# Schematic.net
KiCad netlist of a schematic drawn in Altium Designer
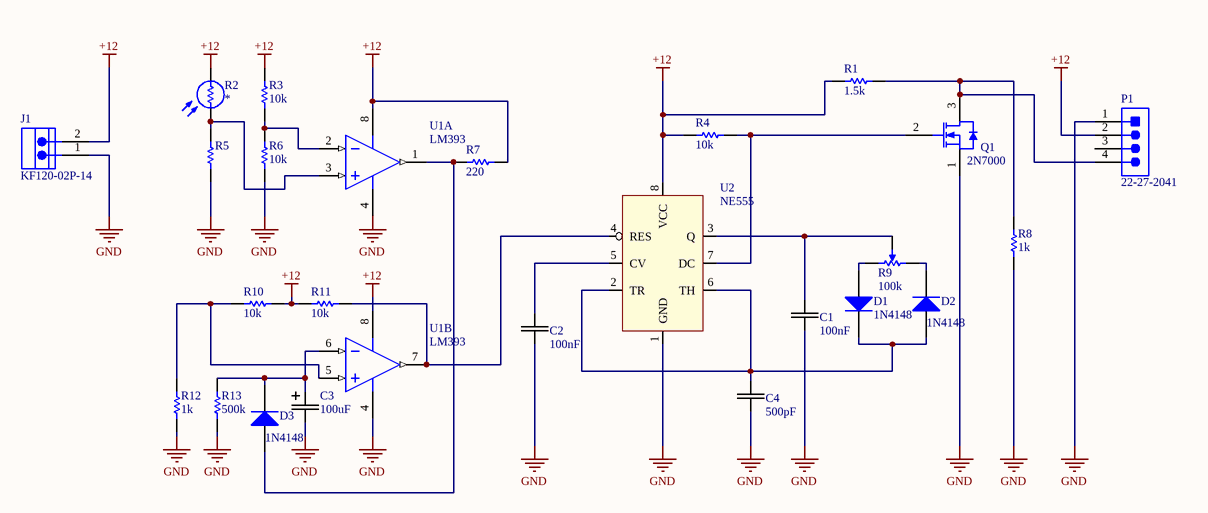
[diagram p0: Schematic.SchDoc]

(export (version "E")
  (design (tool "Eeschema 10.0.6"))
  (components
    (comp (ref "C1")
      (value "CAP_CERAM")
      (footprint "CAP_CERAM")
      (description "Ceramic capacitor")
      (fields (field (name "VAL") "100nF"))
      (libsource (lib "altium-import") (part "root_1_CAP_CERAM_"))
    )
    (comp (ref "C2")
      (value "CAP_CERAM")
      (footprint "CAP_CERAM")
      (description "Ceramic capacitor")
      (fields (field (name "VAL") "100nF"))
      (libsource (lib "altium-import") (part "root_1_CAP_CERAM_"))
    )
    (comp (ref "C3")
      (value "CAP_ELEC_8*11")
      (footprint "CAP_ELEC_8*11")
      (description "Electrolitic capacitor")
      (fields (field (name "VAL") "100uF"))
      (libsource (lib "altium-import") (part "root_1_CAP_ELEC_8*11_"))
    )
    (comp (ref "C4")
      (value "CAP_CERAM")
      (footprint "CAP_CERAM")
      (description "Ceramic capacitor")
      (fields (field (name "VAL") "500pF"))
      (libsource (lib "altium-import") (part "root_1_CAP_CERAM_"))
    )
    (comp (ref "D1")
      (value "1N4148")
      (footprint "DO-41")
      (description "1 A Rectifier Diode, 1000 V, -65 to 175 degC, 2-Pin DO-214AC")
      (fields (field (name "PARTNUMBER") "1N4007") (field (name "MANUFACTURER") "Kesenes"))
      (libsource (lib "altium-import") (part "root_3_1N4007_"))
    )
    (comp (ref "D2")
      (value "1N4148")
      (footprint "DO-41")
      (description "1 A Rectifier Diode, 1000 V, -65 to 175 degC, 2-Pin DO-214AC")
      (fields (field (name "PARTNUMBER") "1N4007") (field (name "MANUFACTURER") "Kesenes"))
      (libsource (lib "altium-import") (part "root_1_1N4007_"))
    )
    (comp (ref "D3")
      (value "1N4148")
      (footprint "DO-41")
      (description "1 A Rectifier Diode, 1000 V, -65 to 175 degC, 2-Pin DO-214AC")
      (fields (field (name "PARTNUMBER") "1N4007") (field (name "MANUFACTURER") "Kesenes"))
      (libsource (lib "altium-import") (part "root_1_1N4007_"))
    )
    (comp (ref "J1")
      (value "KF120-02P-14")
      (footprint "DG301-5.0-02P-1X")
      (fields (field (name "MANUFACTURER") "Cixi KaiFeng") (field (name "CONTACT") "Brass"))
      (libsource (lib "altium-import") (part "root_1_Terminal_2_"))
    )
    (comp (ref "P1")
      (value "22-27-2041")
      (footprint "MOLX-22-27-2041_V")
      (description "Male Header, Pitch 2.54 mm, 1 x 4 Position, Height 11.7 mm, Tail Length 3.56 mm, RoHS, Bulk")
      (fields (field (name "MANUFACTURER") "Molex"))
      (libsource (lib "altium-import") (part "root_0_Molex 1x4 2.54 FAN_"))
    )
    (comp (ref "Q1")
      (value "2N7000")
      (footprint "TO-92A")
      (description "Small Signal MOSFET\r\n200 mAmps, 60 Volts")
      (fields (field (name "MANUFACTURER") "International Rectifier"))
      (libsource (lib "altium-import") (part "root_0_2N7000_"))
    )
    (comp (ref "R1")
      (value "RES-0.125")
      (footprint "RES-0.125")
      (fields (field (name "VAL") "1.5k"))
      (libsource (lib "altium-import") (part "root_2_RES-0.125_"))
    )
    (comp (ref "R2")
      (value "Photoresistor")
      (footprint "Photoresistor")
      (description "PR")
      (fields (field (name "VAL") "*"))
      (libsource (lib "altium-import") (part "root_1_Photoresistor_"))
    )
    (comp (ref "R3")
      (value "RES-0.125")
      (footprint "RES-0.125")
      (fields (field (name "VAL") "10k"))
      (libsource (lib "altium-import") (part "root_1_RES-0.125_"))
    )
    (comp (ref "R4")
      (value "RES-0.125")
      (footprint "RES-0.125")
      (fields (field (name "VAL") "10k"))
      (libsource (lib "altium-import") (part "root_0_RES-0.125_"))
    )
    (comp (ref "R5")
      (value "RES-0.125")
      (footprint "RES-0.125")
      (libsource (lib "altium-import") (part "root_1_RES-0.125_"))
    )
    (comp (ref "R6")
      (value "RES-0.125")
      (footprint "RES-0.125")
      (fields (field (name "VAL") "10k"))
      (libsource (lib "altium-import") (part "root_1_RES-0.125_"))
    )
    (comp (ref "R7")
      (value "RES-0.125")
      (footprint "RES-0.125")
      (fields (field (name "VAL") "220"))
      (libsource (lib "altium-import") (part "root_0_RES-0.125_"))
    )
    (comp (ref "R8")
      (value "RES-0.125")
      (footprint "RES-0.125")
      (fields (field (name "VAL") "1k"))
      (libsource (lib "altium-import") (part "root_1_RES-0.125_"))
    )
    (comp (ref "R9")
      (value "100k")
      (footprint "BOUR-3362P")
      (fields (field (name "Comment") "3296W"))
      (libsource (lib "altium-import") (part "root_2_Potentiometer_"))
    )
    (comp (ref "R10")
      (value "RES-0.125")
      (footprint "RES-0.125")
      (fields (field (name "VAL") "10k"))
      (libsource (lib "altium-import") (part "root_0_RES-0.125_"))
    )
    (comp (ref "R11")
      (value "RES-0.125")
      (footprint "RES-0.125")
      (fields (field (name "VAL") "10k"))
      (libsource (lib "altium-import") (part "root_0_RES-0.125_"))
    )
    (comp (ref "R12")
      (value "RES-0.125")
      (footprint "RES-0.125")
      (fields (field (name "VAL") "1k"))
      (libsource (lib "altium-import") (part "root_1_RES-0.125_"))
    )
    (comp (ref "R13")
      (value "RES-0.125")
      (footprint "RES-0.125")
      (fields (field (name "VAL") "500k"))
      (libsource (lib "altium-import") (part "root_1_RES-0.125_"))
    )
    (comp (ref "U1")
      (value "LM393")
      (footprint "SO-8_N")
      (description "Low Power Low Offset Voltage Dual Comparator, 8-pin Narrow SOIC, Pb-Free")
      (fields (field (name "MANUFACTURER") "Texas Instruments"))
      (libsource (lib "web.skorpio") (part "LM393"))
    )
    (comp (ref "U2")
      (value "NE555")
      (footprint "SOIC8")
      (description "NE555, DIP-8")
      (libsource (lib "altium-import") (part "root_0_NE555_"))
    )
  )
  (nets
    (net (code "1") (name "+12") (class "Default")
      (node (ref "J1") (pin "2") (pinfunction "2_2") (pintype "passive"))
      (node (ref "P1") (pin "2") (pinfunction "2_2") (pintype "passive"))
      (node (ref "R1") (pin "2") (pinfunction "2_2") (pintype "passive"))
      (node (ref "R10") (pin "2") (pinfunction "2_2") (pintype "passive"))
      (node (ref "R11") (pin "1") (pinfunction "1_1") (pintype "passive"))
      (node (ref "R2") (pin "2") (pinfunction "2_2") (pintype "passive"))
      (node (ref "R3") (pin "2") (pinfunction "2_2") (pintype "passive"))
      (node (ref "R4") (pin "1") (pinfunction "1_1") (pintype "passive"))
      (node (ref "R7") (pin "2") (pinfunction "2_2") (pintype "passive"))
      (node (ref "U1") (pin "8") (pinfunction "V+_8") (pintype "power_in"))
      (node (ref "U2") (pin "8") (pinfunction "VCC_8") (pintype "passive"))
    )
    (net (code "2") (name "GND") (class "Default")
      (node (ref "C1") (pin "1") (pinfunction "1_1") (pintype "passive"))
      (node (ref "C2") (pin "1") (pinfunction "1_1") (pintype "passive"))
      (node (ref "C3") (pin "1") (pinfunction "1_1") (pintype "passive"))
      (node (ref "C4") (pin "1") (pinfunction "1_1") (pintype "passive"))
      (node (ref "J1") (pin "1") (pinfunction "1_1") (pintype "passive"))
      (node (ref "P1") (pin "1") (pinfunction "1_1") (pintype "passive"))
      (node (ref "Q1") (pin "1") (pinfunction "S_1") (pintype "passive"))
      (node (ref "R12") (pin "1") (pinfunction "1_1") (pintype "passive"))
      (node (ref "R13") (pin "1") (pinfunction "1_1") (pintype "passive"))
      (node (ref "R5") (pin "1") (pinfunction "1_1") (pintype "passive"))
      (node (ref "R6") (pin "1") (pinfunction "1_1") (pintype "passive"))
      (node (ref "R8") (pin "1") (pinfunction "1_1") (pintype "passive"))
      (node (ref "U1") (pin "4") (pinfunction "GND_4") (pintype "power_in"))
      (node (ref "U2") (pin "1") (pinfunction "GND_1") (pintype "passive"))
    )
    (net (code "3") (name "Net-(D1-A)") (class "Default")
      (node (ref "D1") (pin "2") (pinfunction "A_2") (pintype "passive"))
      (node (ref "R9") (pin "3") (pinfunction "3_3") (pintype "passive"))
    )
    (net (code "4") (name "Net-(D1-K)") (class "Default")
      (node (ref "C4") (pin "2") (pinfunction "2_2") (pintype "passive"))
      (node (ref "D1") (pin "1") (pinfunction "K_1") (pintype "passive"))
      (node (ref "D2") (pin "2") (pinfunction "A_2") (pintype "passive"))
      (node (ref "U2") (pin "2") (pinfunction "TR_2") (pintype "passive"))
      (node (ref "U2") (pin "6") (pinfunction "TH_6") (pintype "passive"))
    )
    (net (code "5") (name "Net-(D2-K)") (class "Default")
      (node (ref "D2") (pin "1") (pinfunction "K_1") (pintype "passive"))
      (node (ref "R9") (pin "1") (pinfunction "1_1") (pintype "passive"))
    )
    (net (code "6") (name "Net-(D3-A)") (class "Default")
      (node (ref "D3") (pin "2") (pinfunction "A_2") (pintype "passive"))
      (node (ref "R7") (pin "1") (pinfunction "1_1") (pintype "passive"))
      (node (ref "U1") (pin "1") (pinfunction "OUTA_1") (pintype "output"))
    )
    (net (code "7") (name "Net-(D3-K)") (class "Default")
      (node (ref "C3") (pin "2") (pinfunction "2_2") (pintype "passive"))
      (node (ref "D3") (pin "1") (pinfunction "K_1") (pintype "passive"))
      (node (ref "R13") (pin "2") (pinfunction "2_2") (pintype "passive"))
      (node (ref "U1") (pin "6") (pinfunction "INB-_6") (pintype "input"))
    )
    (net (code "8") (name "Net-(Q1-D)") (class "Default")
      (node (ref "P1") (pin "4") (pinfunction "4_4") (pintype "passive"))
      (node (ref "Q1") (pin "3") (pinfunction "D_3") (pintype "passive"))
      (node (ref "R1") (pin "1") (pinfunction "1_1") (pintype "passive"))
      (node (ref "R8") (pin "2") (pinfunction "2_2") (pintype "passive"))
    )
    (net (code "9") (name "Net-(Q1-G)") (class "Default")
      (node (ref "Q1") (pin "2") (pinfunction "G_2") (pintype "passive"))
      (node (ref "R4") (pin "2") (pinfunction "2_2") (pintype "passive"))
      (node (ref "U2") (pin "7") (pinfunction "DC_7") (pintype "passive"))
    )
    (net (code "10") (name "Net-(U1A-INA+)") (class "Default")
      (node (ref "R2") (pin "1") (pinfunction "1_1") (pintype "passive"))
      (node (ref "R5") (pin "2") (pinfunction "2_2") (pintype "passive"))
      (node (ref "U1") (pin "3") (pinfunction "INA+_3") (pintype "input"))
    )
    (net (code "11") (name "Net-(U1A-INA-)") (class "Default")
      (node (ref "R3") (pin "1") (pinfunction "1_1") (pintype "passive"))
      (node (ref "R6") (pin "2") (pinfunction "2_2") (pintype "passive"))
      (node (ref "U1") (pin "2") (pinfunction "INA-_2") (pintype "input"))
    )
    (net (code "12") (name "Net-(U1B-INB+)") (class "Default")
      (node (ref "R10") (pin "1") (pinfunction "1_1") (pintype "passive"))
      (node (ref "R12") (pin "2") (pinfunction "2_2") (pintype "passive"))
      (node (ref "U1") (pin "5") (pinfunction "INB+_5") (pintype "input"))
    )
    (net (code "13") (name "Net-(U1B-OUTB)") (class "Default")
      (node (ref "R11") (pin "2") (pinfunction "2_2") (pintype "passive"))
      (node (ref "U1") (pin "7") (pinfunction "OUTB_7") (pintype "output"))
      (node (ref "U2") (pin "4") (pinfunction "RES_4") (pintype "passive"))
    )
    (net (code "14") (name "Net-(U2-CV)") (class "Default")
      (node (ref "C2") (pin "2") (pinfunction "2_2") (pintype "passive"))
      (node (ref "U2") (pin "5") (pinfunction "CV_5") (pintype "passive"))
    )
    (net (code "15") (name "Net-(U2-Q)") (class "Default")
      (node (ref "C1") (pin "2") (pinfunction "2_2") (pintype "passive"))
      (node (ref "R9") (pin "2") (pinfunction "2_2") (pintype "passive"))
      (node (ref "U2") (pin "3") (pinfunction "Q_3") (pintype "passive"))
    )
    (net (code "16") (name "unconnected-(P1-Pad3)") (class "Default")
      (node (ref "P1") (pin "3") (pinfunction "3_3") (pintype "passive"))
    )
  )
)
